# Rev_A.net
KiCad netlist of a schematic drawn in EAGLE
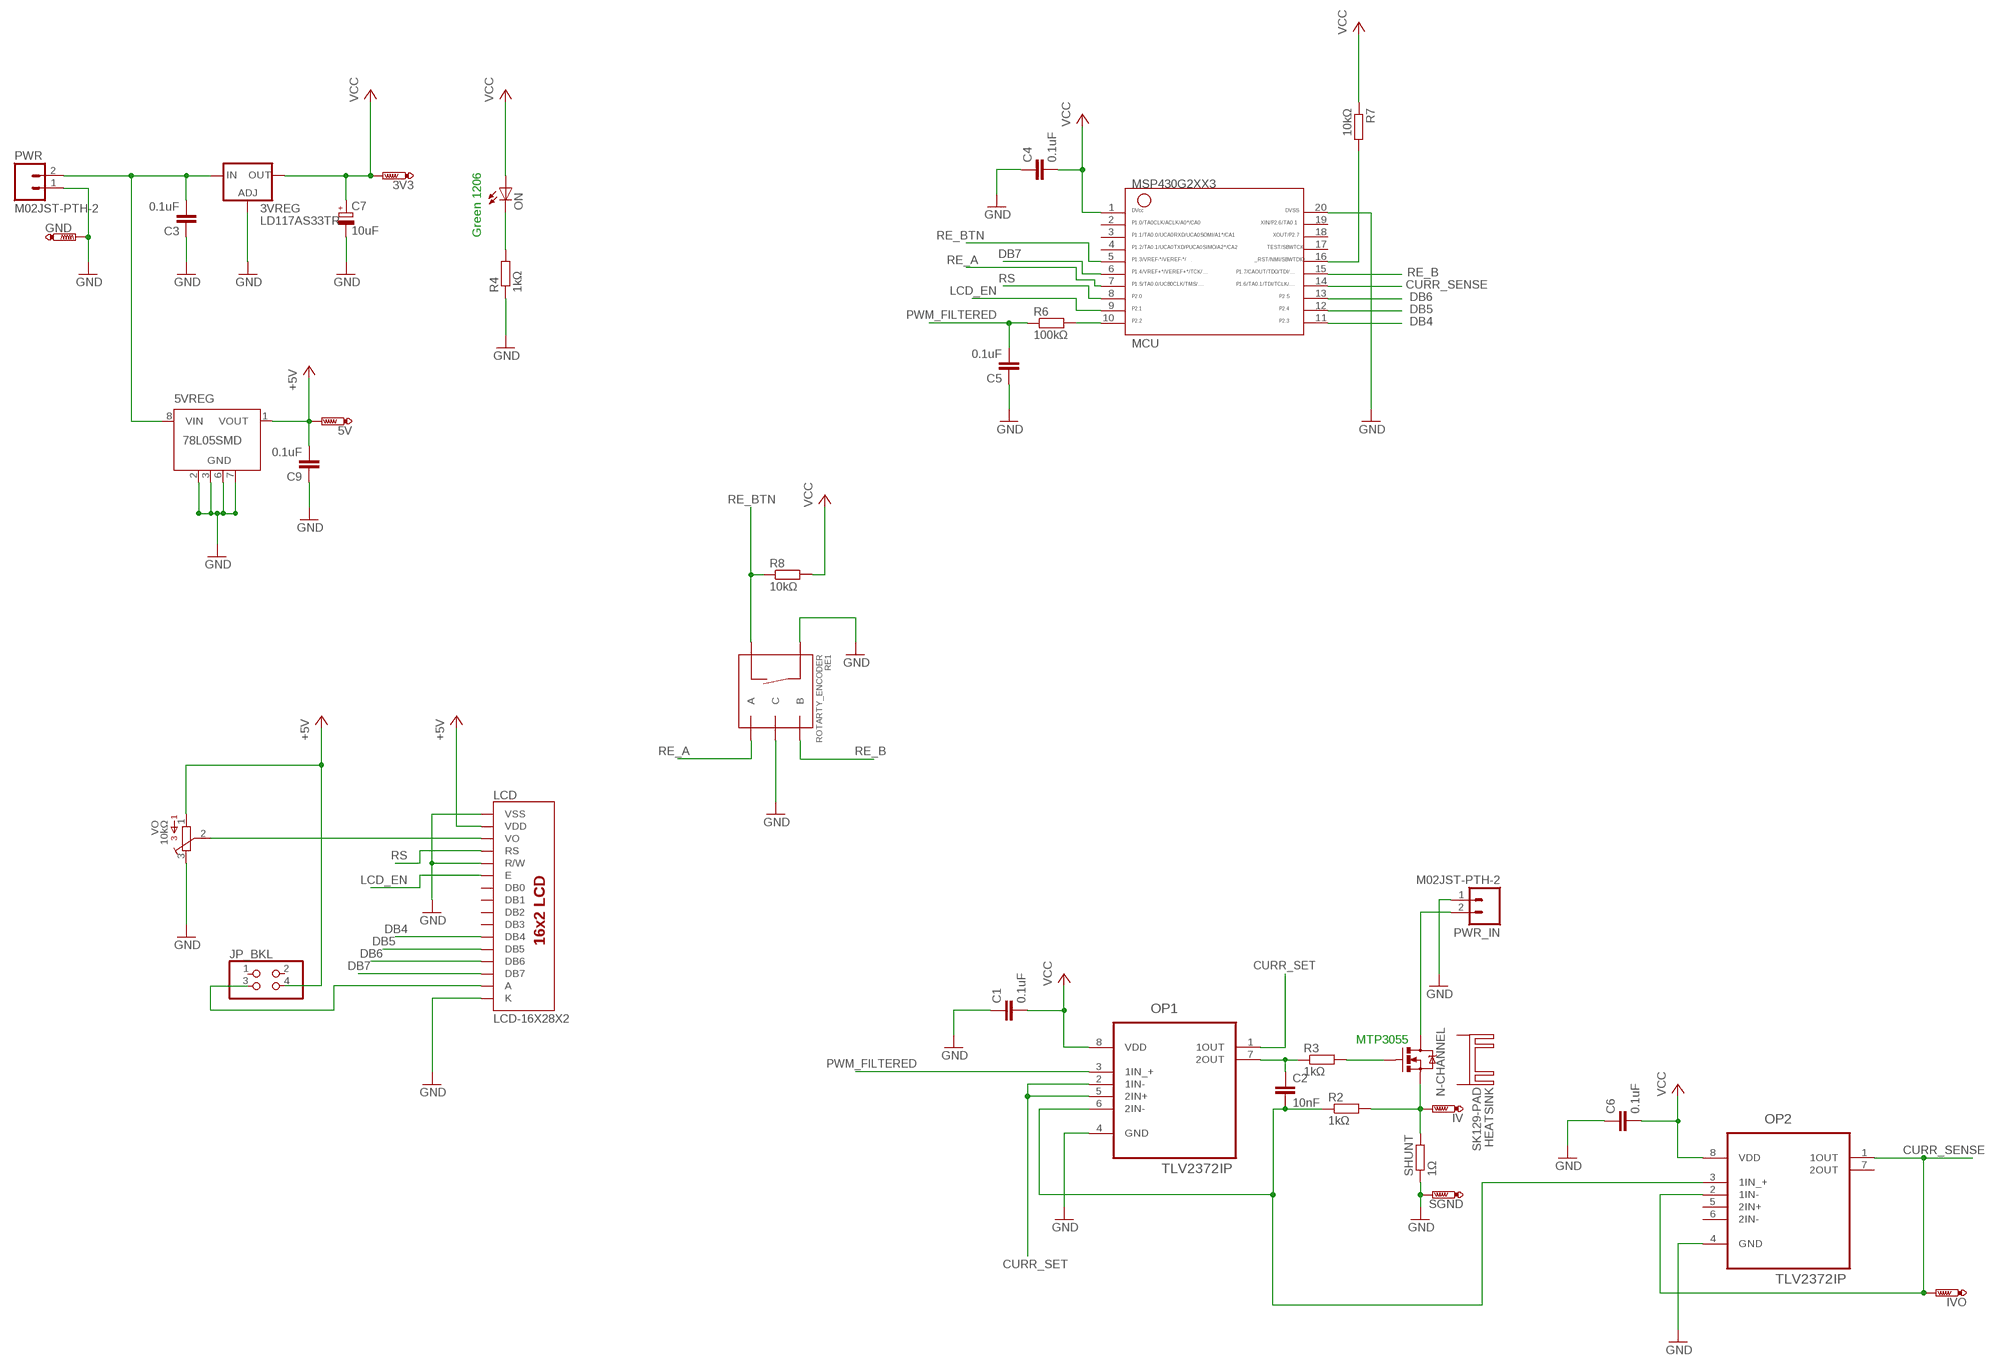
[diagram p0: schematic, sheet 1]

(export (version "E")
  (design (tool "Eeschema 10.0.6"))
  (components
    (comp (ref "3V3")
      (value "PTR1TP10SQ")
      (footprint "eagle-import:TP10SQ")
      (libsource (lib "eagle-import") (part "PTR1TP10SQ"))
    )
    (comp (ref "3VREG")
      (value "LD117AS33TR")
      (footprint "eagle-import:SOT223")
      (libsource (lib "eagle-import") (part "LD117A?S33TR"))
    )
    (comp (ref "5V")
      (value "PTR1TP10SQ")
      (footprint "eagle-import:TP10SQ")
      (libsource (lib "eagle-import") (part "PTR1TP10SQ"))
    )
    (comp (ref "5VREG")
      (value "78L05SMD")
      (footprint "eagle-import:SO08")
      (libsource (lib "eagle-import") (part "78LSMD05"))
    )
    (comp (ref "C1")
      (value "0.1uF")
      (footprint "eagle-import:C0805")
      (libsource (lib "eagle-import") (part "C-EUC0805"))
    )
    (comp (ref "C2")
      (value "10nF")
      (footprint "eagle-import:C0805")
      (libsource (lib "eagle-import") (part "C-EUC0805"))
    )
    (comp (ref "C3")
      (value "0.1uF")
      (footprint "eagle-import:C0805")
      (libsource (lib "eagle-import") (part "C-EUC0805"))
    )
    (comp (ref "C4")
      (value "0.1uF")
      (footprint "eagle-import:C0805")
      (libsource (lib "eagle-import") (part "C-EUC0805"))
    )
    (comp (ref "C5")
      (value "0.1uF")
      (footprint "eagle-import:C0805")
      (libsource (lib "eagle-import") (part "C-EUC0805"))
    )
    (comp (ref "C6")
      (value "0.1uF")
      (footprint "eagle-import:C0805")
      (libsource (lib "eagle-import") (part "C-EUC0805"))
    )
    (comp (ref "C7")
      (value "10uF")
      (footprint "eagle-import:E2,5-6")
      (libsource (lib "eagle-import") (part "CPOL-EUE2.5-6"))
    )
    (comp (ref "C9")
      (value "0.1uF")
      (footprint "eagle-import:C0805")
      (libsource (lib "eagle-import") (part "C-EUC0805"))
    )
    (comp (ref "GND")
      (value "PTR1TP10SQ")
      (footprint "eagle-import:TP10SQ")
      (libsource (lib "eagle-import") (part "PTR1TP10SQ"))
    )
    (comp (ref "HEATSINK")
      (value "SK129-PAD")
      (footprint "eagle-import:SK129")
      (libsource (lib "eagle-import") (part "SK129-PAD"))
    )
    (comp (ref "IV")
      (value "PTR1TP10SQ")
      (footprint "eagle-import:TP10SQ")
      (libsource (lib "eagle-import") (part "PTR1TP10SQ"))
    )
    (comp (ref "IVO")
      (value "PTR1TP10SQ")
      (footprint "eagle-import:TP10SQ")
      (libsource (lib "eagle-import") (part "PTR1TP10SQ"))
    )
    (comp (ref "JP_BKL")
      (value "PINHD-2X2")
      (footprint "eagle-import:2X02")
      (libsource (lib "eagle-import") (part "PINHD-2X2"))
    )
    (comp (ref "LCD")
      (value "LCD-16X28X2")
      (footprint "eagle-import:LCD-8X2")
      (libsource (lib "eagle-import") (part "LCD-16X28X2"))
    )
    (comp (ref "MCU")
      (value "G2XX3---N20")
      (footprint "eagle-import:N20")
      (libsource (lib "eagle-import") (part "G2XX3---N20"))
    )
    (comp (ref "N-CHANNEL")
      (value "MOSFET-NCHANNELFQP30N06L")
      (footprint "eagle-import:TO220V")
      (libsource (lib "eagle-import") (part "MOSFET-NCHANNELFQP30N06L"))
    )
    (comp (ref "ON")
      (value "LEDCHIPLED_1206")
      (footprint "eagle-import:CHIPLED_1206")
      (libsource (lib "eagle-import") (part "LEDCHIPLED_1206"))
    )
    (comp (ref "OP1")
      (value "TLV2372IP")
      (footprint "eagle-import:DIP254P762X508-8")
      (libsource (lib "eagle-import") (part "TLV2372IP"))
    )
    (comp (ref "OP2")
      (value "TLV2372IP")
      (footprint "eagle-import:DIP254P762X508-8")
      (libsource (lib "eagle-import") (part "TLV2372IP"))
    )
    (comp (ref "PWR")
      (value "M02JST-PTH-2")
      (footprint "eagle-import:JST-2-PTH")
      (libsource (lib "eagle-import") (part "M02JST-PTH-2"))
    )
    (comp (ref "PWR_IN")
      (value "M02JST-PTH-2")
      (footprint "eagle-import:JST-2-PTH")
      (libsource (lib "eagle-import") (part "M02JST-PTH-2"))
    )
    (comp (ref "R2")
      (value "1kΩ")
      (footprint "eagle-import:R0805")
      (libsource (lib "eagle-import") (part "R-EU_R0805"))
    )
    (comp (ref "R3")
      (value "1kΩ")
      (footprint "eagle-import:R0805")
      (libsource (lib "eagle-import") (part "R-EU_R0805"))
    )
    (comp (ref "R4")
      (value "1kΩ")
      (footprint "eagle-import:R0805")
      (libsource (lib "eagle-import") (part "R-EU_R0805"))
    )
    (comp (ref "R6")
      (value "100kΩ")
      (footprint "eagle-import:R0805")
      (libsource (lib "eagle-import") (part "R-EU_R0805"))
    )
    (comp (ref "R7")
      (value "10kΩ")
      (footprint "eagle-import:R0805")
      (libsource (lib "eagle-import") (part "resistor_R-EU_R0805"))
    )
    (comp (ref "R8")
      (value "10kΩ")
      (footprint "eagle-import:R0805")
      (libsource (lib "eagle-import") (part "R-EU_R0805"))
    )
    (comp (ref "RE1")
      (value "ROTARTY_ENCODER")
      (footprint "eagle-import:ROTARY_ENC_PLAIN")
      (libsource (lib "eagle-import") (part "ROTARTY_ENCODER"))
    )
    (comp (ref "SGND")
      (value "PTR1TP10SQ")
      (footprint "eagle-import:TP10SQ")
      (libsource (lib "eagle-import") (part "PTR1TP10SQ"))
    )
    (comp (ref "SHUNT")
      (value "1Ω")
      (footprint "eagle-import:VTA52")
      (libsource (lib "eagle-import") (part "R-EU_VTA52"))
    )
    (comp (ref "VO")
      (value "10kΩ")
      (footprint "eagle-import:3386G")
      (libsource (lib "eagle-import") (part "3386-G"))
    )
  )
  (nets
    (net (code "1") (name "+5V") (class "Default")
      (node (ref "5V") (pin "TP") (pinfunction "TP_TP") (pintype "input"))
      (node (ref "5VREG") (pin "1") (pinfunction "VOUT_1") (pintype "output"))
      (node (ref "C9") (pin "2") (pinfunction "2_2") (pintype "passive"))
      (node (ref "JP_BKL") (pin "4") (pinfunction "4_4") (pintype "passive"))
      (node (ref "LCD") (pin "2") (pinfunction "VDD_2") (pintype "power_in"))
      (node (ref "VO") (pin "1") (pinfunction "1_1") (pintype "passive"))
    )
    (net (code "2") (name "/CURR_SENSE") (class "Default")
      (node (ref "IVO") (pin "TP") (pinfunction "TP_TP") (pintype "input"))
      (node (ref "MCU") (pin "14") (pinfunction "14_14") (pintype "bidirectional"))
      (node (ref "OP2") (pin "1") (pinfunction "1OUT_1") (pintype "output"))
      (node (ref "OP2") (pin "2") (pinfunction "1IN-_2") (pintype "input"))
    )
    (net (code "3") (name "/CURR_SET") (class "Default")
      (node (ref "OP1") (pin "1") (pinfunction "1OUT_1") (pintype "output"))
      (node (ref "OP1") (pin "2") (pinfunction "1IN-_2") (pintype "input"))
      (node (ref "OP1") (pin "5") (pinfunction "2IN+_5") (pintype "input"))
    )
    (net (code "4") (name "/DB4") (class "Default")
      (node (ref "LCD") (pin "11") (pinfunction "DB4_11") (pintype "bidirectional"))
      (node (ref "MCU") (pin "11") (pinfunction "11_11") (pintype "bidirectional"))
    )
    (net (code "5") (name "/DB5") (class "Default")
      (node (ref "LCD") (pin "12") (pinfunction "DB5_12") (pintype "bidirectional"))
      (node (ref "MCU") (pin "12") (pinfunction "12_12") (pintype "bidirectional"))
    )
    (net (code "6") (name "/DB6") (class "Default")
      (node (ref "LCD") (pin "13") (pinfunction "DB6_13") (pintype "bidirectional"))
      (node (ref "MCU") (pin "13") (pinfunction "13_13") (pintype "bidirectional"))
    )
    (net (code "7") (name "/DB7") (class "Default")
      (node (ref "LCD") (pin "14") (pinfunction "DB7_14") (pintype "bidirectional"))
      (node (ref "MCU") (pin "6") (pinfunction "6_6") (pintype "bidirectional"))
    )
    (net (code "8") (name "/LCD_EN") (class "Default")
      (node (ref "LCD") (pin "6") (pinfunction "E_6") (pintype "input"))
      (node (ref "MCU") (pin "9") (pinfunction "9_9") (pintype "bidirectional"))
    )
    (net (code "9") (name "/PWM_FILTERED") (class "Default")
      (node (ref "C5") (pin "2") (pinfunction "2_2") (pintype "passive"))
      (node (ref "OP1") (pin "3") (pinfunction "1IN_+_3") (pintype "input"))
      (node (ref "R6") (pin "1") (pinfunction "1_1") (pintype "passive"))
    )
    (net (code "10") (name "/RE_A") (class "Default")
      (node (ref "MCU") (pin "7") (pinfunction "7_7") (pintype "bidirectional"))
      (node (ref "RE1") (pin "A") (pinfunction "A_A") (pintype "bidirectional"))
    )
    (net (code "11") (name "/RE_B") (class "Default")
      (node (ref "MCU") (pin "15") (pinfunction "15_15") (pintype "bidirectional"))
      (node (ref "RE1") (pin "B") (pinfunction "B_B") (pintype "bidirectional"))
    )
    (net (code "12") (name "/RE_BTN") (class "Default")
      (node (ref "MCU") (pin "5") (pinfunction "5_5") (pintype "bidirectional"))
      (node (ref "R8") (pin "1") (pinfunction "1_1") (pintype "passive"))
      (node (ref "RE1") (pin "SW-") (pinfunction "SW-_SW-") (pintype "bidirectional"))
    )
    (net (code "13") (name "/RS") (class "Default")
      (node (ref "LCD") (pin "4") (pinfunction "RS_4") (pintype "input"))
      (node (ref "MCU") (pin "8") (pinfunction "8_8") (pintype "bidirectional"))
    )
    (net (code "14") (name "GND") (class "Default")
      (node (ref "3VREG") (pin "1") (pinfunction "ADJ_1") (pintype "input"))
      (node (ref "5VREG") (pin "2") (pinfunction "GND_2") (pintype "power_in"))
      (node (ref "5VREG") (pin "3") (pinfunction "GND_3") (pintype "power_in"))
      (node (ref "5VREG") (pin "6") (pinfunction "GND_6") (pintype "power_in"))
      (node (ref "5VREG") (pin "7") (pinfunction "GND_7") (pintype "power_in"))
      (node (ref "C1") (pin "1") (pinfunction "1_1") (pintype "passive"))
      (node (ref "C3") (pin "1") (pinfunction "1_1") (pintype "passive"))
      (node (ref "C4") (pin "1") (pinfunction "1_1") (pintype "passive"))
      (node (ref "C5") (pin "1") (pinfunction "1_1") (pintype "passive"))
      (node (ref "C6") (pin "1") (pinfunction "1_1") (pintype "passive"))
      (node (ref "C7") (pin "-") (pinfunction "-_-") (pintype "passive"))
      (node (ref "C9") (pin "1") (pinfunction "1_1") (pintype "passive"))
      (node (ref "GND") (pin "TP") (pinfunction "TP_TP") (pintype "input"))
      (node (ref "LCD") (pin "1") (pinfunction "VSS_1") (pintype "power_in"))
      (node (ref "LCD") (pin "16") (pinfunction "K_16") (pintype "power_in"))
      (node (ref "LCD") (pin "5") (pinfunction "R/W_5") (pintype "input"))
      (node (ref "MCU") (pin "20") (pinfunction "20_20") (pintype "bidirectional"))
      (node (ref "OP1") (pin "4") (pinfunction "GND_4") (pintype "passive"))
      (node (ref "OP2") (pin "4") (pinfunction "GND_4") (pintype "passive"))
      (node (ref "PWR") (pin "1") (pinfunction "1_1") (pintype "passive"))
      (node (ref "PWR_IN") (pin "1") (pinfunction "1_1") (pintype "passive"))
      (node (ref "R4") (pin "1") (pinfunction "1_1") (pintype "passive"))
      (node (ref "RE1") (pin "C") (pinfunction "C_C") (pintype "bidirectional"))
      (node (ref "RE1") (pin "SW+") (pinfunction "SW+_SW+") (pintype "bidirectional"))
      (node (ref "SGND") (pin "TP") (pinfunction "TP_TP") (pintype "input"))
      (node (ref "SHUNT") (pin "1") (pinfunction "1_1") (pintype "passive"))
      (node (ref "VO") (pin "3") (pinfunction "3_3") (pintype "passive"))
    )
    (net (code "15") (name "Net-(3VREG-IN)") (class "Default")
      (node (ref "3VREG") (pin "3") (pinfunction "IN_3") (pintype "input"))
      (node (ref "5VREG") (pin "8") (pinfunction "VIN_8") (pintype "passive"))
      (node (ref "C3") (pin "2") (pinfunction "2_2") (pintype "passive"))
      (node (ref "PWR") (pin "2") (pinfunction "2_2") (pintype "passive"))
    )
    (net (code "16") (name "Net-(LCD-A)") (class "Default")
      (node (ref "JP_BKL") (pin "3") (pinfunction "3_3") (pintype "passive"))
      (node (ref "LCD") (pin "15") (pinfunction "A_15") (pintype "power_in"))
    )
    (net (code "17") (name "Net-(LCD-VO)") (class "Default")
      (node (ref "LCD") (pin "3") (pinfunction "VO_3") (pintype "bidirectional"))
      (node (ref "VO") (pin "2") (pinfunction "2_2") (pintype "passive"))
    )
    (net (code "18") (name "Net-(MCU-Pad10)") (class "Default")
      (node (ref "MCU") (pin "10") (pinfunction "10_10") (pintype "bidirectional"))
      (node (ref "R6") (pin "2") (pinfunction "2_2") (pintype "passive"))
    )
    (net (code "19") (name "Net-(MCU-Pad16)") (class "Default")
      (node (ref "MCU") (pin "16") (pinfunction "16_16") (pintype "bidirectional"))
      (node (ref "R7") (pin "2") (pinfunction "2_2") (pintype "passive"))
    )
    (net (code "20") (name "Net-(N-CHANNEL-D)") (class "Default")
      (node (ref "N-CHANNEL") (pin "2") (pinfunction "D_2") (pintype "passive"))
      (node (ref "PWR_IN") (pin "2") (pinfunction "2_2") (pintype "passive"))
    )
    (net (code "21") (name "Net-(N-CHANNEL-G)") (class "Default")
      (node (ref "N-CHANNEL") (pin "1") (pinfunction "G_1") (pintype "passive"))
      (node (ref "R3") (pin "2") (pinfunction "2_2") (pintype "passive"))
    )
    (net (code "22") (name "Net-(N-CHANNEL-S)") (class "Default")
      (node (ref "IV") (pin "TP") (pinfunction "TP_TP") (pintype "input"))
      (node (ref "N-CHANNEL") (pin "3") (pinfunction "S_3") (pintype "passive"))
      (node (ref "R2") (pin "2") (pinfunction "2_2") (pintype "passive"))
      (node (ref "SHUNT") (pin "2") (pinfunction "2_2") (pintype "passive"))
    )
    (net (code "23") (name "Net-(ON-PadC)") (class "Default")
      (node (ref "ON") (pin "C") (pinfunction "C_C") (pintype "passive"))
      (node (ref "R4") (pin "2") (pinfunction "2_2") (pintype "passive"))
    )
    (net (code "24") (name "Net-(OP1-2IN-)") (class "Default")
      (node (ref "C2") (pin "2") (pinfunction "2_2") (pintype "passive"))
      (node (ref "OP1") (pin "6") (pinfunction "2IN-_6") (pintype "input"))
      (node (ref "OP2") (pin "3") (pinfunction "1IN_+_3") (pintype "input"))
      (node (ref "R2") (pin "1") (pinfunction "1_1") (pintype "passive"))
    )
    (net (code "25") (name "Net-(OP1-2OUT)") (class "Default")
      (node (ref "C2") (pin "1") (pinfunction "1_1") (pintype "passive"))
      (node (ref "OP1") (pin "7") (pinfunction "2OUT_7") (pintype "output"))
      (node (ref "R3") (pin "1") (pinfunction "1_1") (pintype "passive"))
    )
    (net (code "26") (name "VCC") (class "Default")
      (node (ref "3V3") (pin "TP") (pinfunction "TP_TP") (pintype "input"))
      (node (ref "3VREG") (pin "4") (pinfunction "OUT_4") (pintype "passive"))
      (node (ref "C1") (pin "2") (pinfunction "2_2") (pintype "passive"))
      (node (ref "C4") (pin "2") (pinfunction "2_2") (pintype "passive"))
      (node (ref "C6") (pin "2") (pinfunction "2_2") (pintype "passive"))
      (node (ref "C7") (pin "+") (pinfunction "+_+") (pintype "passive"))
      (node (ref "MCU") (pin "1") (pinfunction "1_1") (pintype "bidirectional"))
      (node (ref "ON") (pin "A") (pinfunction "A_A") (pintype "passive"))
      (node (ref "OP1") (pin "8") (pinfunction "VDD_8") (pintype "power_in"))
      (node (ref "OP2") (pin "8") (pinfunction "VDD_8") (pintype "power_in"))
      (node (ref "R7") (pin "1") (pinfunction "1_1") (pintype "passive"))
      (node (ref "R8") (pin "2") (pinfunction "2_2") (pintype "passive"))
    )
    (net (code "27") (name "unconnected-(HEATSINK-K-PadA2,5)") (class "Default")
      (node (ref "HEATSINK") (pin "A2,5") (pinfunction "K_A2,5") (pintype "passive"))
    )
    (net (code "28") (name "unconnected-(HEATSINK-K-PadB2,5)") (class "Default")
      (node (ref "HEATSINK") (pin "B2,5") (pinfunction "K_B2,5") (pintype "passive"))
    )
    (net (code "29") (name "unconnected-(JP_BKL-Pad1)") (class "Default")
      (node (ref "JP_BKL") (pin "1") (pinfunction "1_1") (pintype "passive"))
    )
    (net (code "30") (name "unconnected-(JP_BKL-Pad2)") (class "Default")
      (node (ref "JP_BKL") (pin "2") (pinfunction "2_2") (pintype "passive"))
    )
    (net (code "31") (name "unconnected-(LCD-DB0-Pad7)") (class "Default")
      (node (ref "LCD") (pin "7") (pinfunction "DB0_7") (pintype "bidirectional"))
    )
    (net (code "32") (name "unconnected-(LCD-DB1-Pad8)") (class "Default")
      (node (ref "LCD") (pin "8") (pinfunction "DB1_8") (pintype "bidirectional"))
    )
    (net (code "33") (name "unconnected-(LCD-DB2-Pad9)") (class "Default")
      (node (ref "LCD") (pin "9") (pinfunction "DB2_9") (pintype "bidirectional"))
    )
    (net (code "34") (name "unconnected-(LCD-DB3-Pad10)") (class "Default")
      (node (ref "LCD") (pin "10") (pinfunction "DB3_10") (pintype "bidirectional"))
    )
    (net (code "35") (name "unconnected-(MCU-Pad2)") (class "Default")
      (node (ref "MCU") (pin "2") (pinfunction "2_2") (pintype "bidirectional"))
    )
    (net (code "36") (name "unconnected-(MCU-Pad3)") (class "Default")
      (node (ref "MCU") (pin "3") (pinfunction "3_3") (pintype "bidirectional"))
    )
    (net (code "37") (name "unconnected-(MCU-Pad4)") (class "Default")
      (node (ref "MCU") (pin "4") (pinfunction "4_4") (pintype "bidirectional"))
    )
    (net (code "38") (name "unconnected-(MCU-Pad17)") (class "Default")
      (node (ref "MCU") (pin "17") (pinfunction "17_17") (pintype "bidirectional"))
    )
    (net (code "39") (name "unconnected-(MCU-Pad18)") (class "Default")
      (node (ref "MCU") (pin "18") (pinfunction "18_18") (pintype "bidirectional"))
    )
    (net (code "40") (name "unconnected-(MCU-Pad19)") (class "Default")
      (node (ref "MCU") (pin "19") (pinfunction "19_19") (pintype "bidirectional"))
    )
    (net (code "41") (name "unconnected-(OP2-2IN+-Pad5)") (class "Default")
      (node (ref "OP2") (pin "5") (pinfunction "2IN+_5") (pintype "input"))
    )
    (net (code "42") (name "unconnected-(OP2-2IN--Pad6)") (class "Default")
      (node (ref "OP2") (pin "6") (pinfunction "2IN-_6") (pintype "input"))
    )
    (net (code "43") (name "unconnected-(OP2-2OUT-Pad7)") (class "Default")
      (node (ref "OP2") (pin "7") (pinfunction "2OUT_7") (pintype "output"))
    )
  )
)
